# project.net
KiCad netlist of a schematic drawn in EAGLE
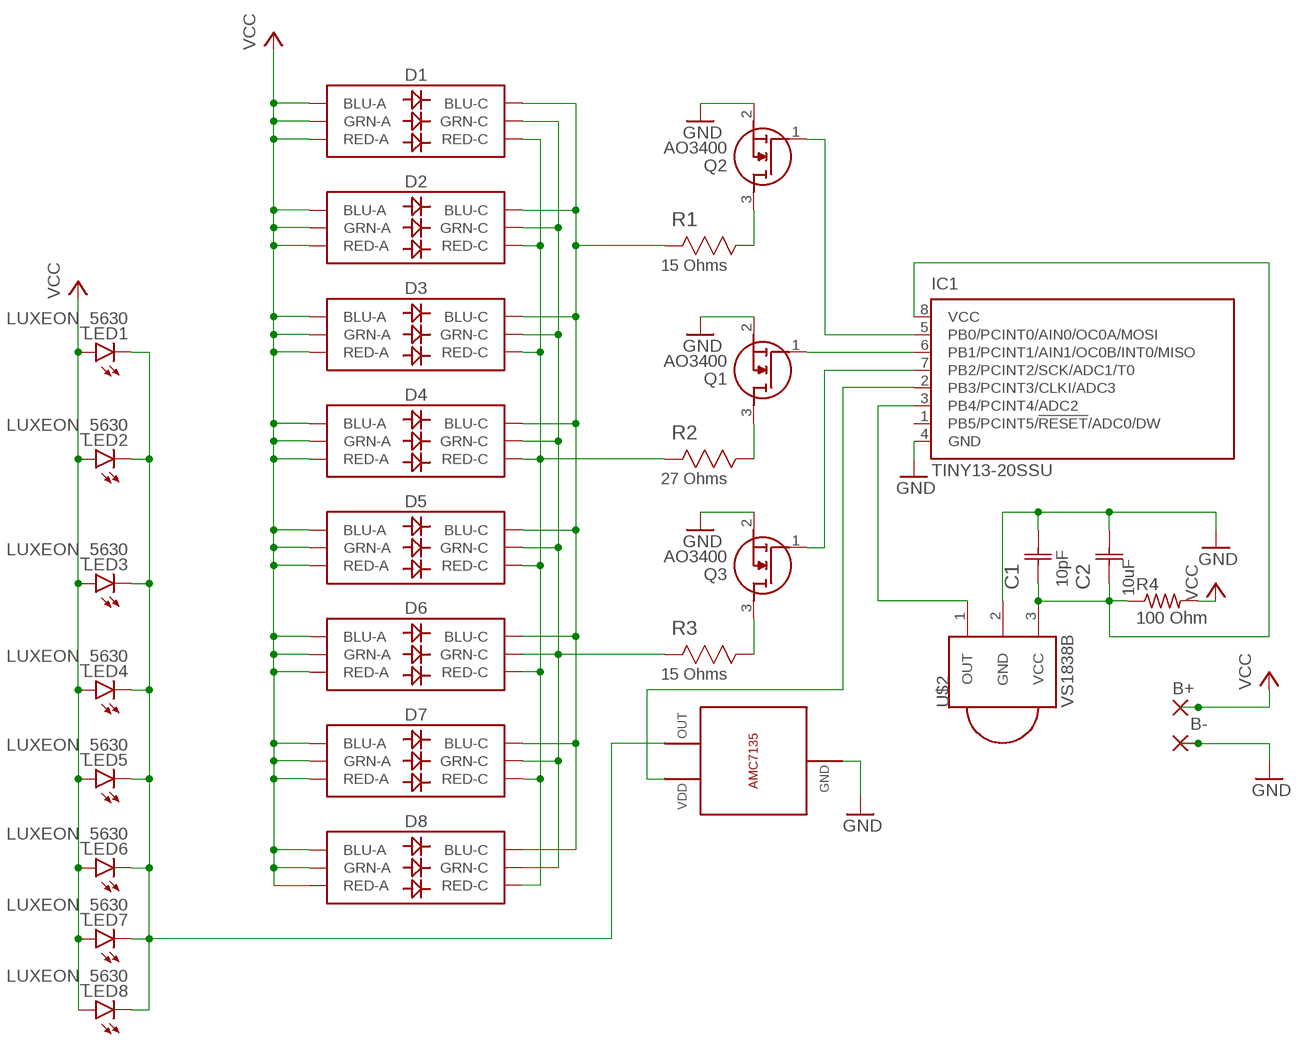
[diagram p0: schematic, sheet 1]

(export (version "E")
  (design (tool "Eeschema 10.0.6"))
  (components
    (comp (ref "B+")
      (value "WIREPADSMD1,27-254")
      (footprint "eagle-import:SMD1,27-2,54")
      (libsource (lib "eagle-import") (part "WIREPADSMD1,27-254"))
    )
    (comp (ref "B-")
      (value "WIREPADSMD1,27-254")
      (footprint "eagle-import:SMD1,27-2,54")
      (libsource (lib "eagle-import") (part "WIREPADSMD1,27-254"))
    )
    (comp (ref "C1")
      (value "10pF")
      (footprint "eagle-import:CAPC2013X94N")
      (fields (field (name "MPN") "08051A100JAT2A") (field (name "TOLERANCE") "±5%"))
      (libsource (lib "eagle-import") (part "08051A100JAT2A"))
    )
    (comp (ref "C2")
      (value "10uF")
      (footprint "eagle-import:CAPC3216X94N")
      (fields (field (name "MPN") "12061A101JAT2A") (field (name "TOLERANCE") "±5%"))
      (libsource (lib "eagle-import") (part "12061A101JAT2A"))
    )
    (comp (ref "D1")
      (value "LED-RGBNO_IC")
      (footprint "eagle-import:LED-TRICOLOR-5050")
      (libsource (lib "eagle-import") (part "LED-RGBNO_IC"))
    )
    (comp (ref "D2")
      (value "LED-RGBNO_IC")
      (footprint "eagle-import:LED-TRICOLOR-5050")
      (libsource (lib "eagle-import") (part "LED-RGBNO_IC"))
    )
    (comp (ref "D3")
      (value "LED-RGBNO_IC")
      (footprint "eagle-import:LED-TRICOLOR-5050")
      (libsource (lib "eagle-import") (part "LED-RGBNO_IC"))
    )
    (comp (ref "D4")
      (value "LED-RGBNO_IC")
      (footprint "eagle-import:LED-TRICOLOR-5050")
      (libsource (lib "eagle-import") (part "LED-RGBNO_IC"))
    )
    (comp (ref "D5")
      (value "LED-RGBNO_IC")
      (footprint "eagle-import:LED-TRICOLOR-5050")
      (libsource (lib "eagle-import") (part "LED-RGBNO_IC"))
    )
    (comp (ref "D6")
      (value "LED-RGBNO_IC")
      (footprint "eagle-import:LED-TRICOLOR-5050")
      (libsource (lib "eagle-import") (part "LED-RGBNO_IC"))
    )
    (comp (ref "D7")
      (value "LED-RGBNO_IC")
      (footprint "eagle-import:LED-TRICOLOR-5050")
      (libsource (lib "eagle-import") (part "LED-RGBNO_IC"))
    )
    (comp (ref "D8")
      (value "LED-RGBNO_IC")
      (footprint "eagle-import:LED-TRICOLOR-5050")
      (libsource (lib "eagle-import") (part "LED-RGBNO_IC"))
    )
    (comp (ref "IC1")
      (value "TINY13-20SSU")
      (footprint "eagle-import:8S1")
      (fields (field (name "MPN") "ATTINY13-20SSU"))
      (libsource (lib "eagle-import") (part "TINY13SSU-20"))
    )
    (comp (ref "LED1")
      (value "LUXEON_5630")
      (footprint "eagle-import:LUXEON_5630")
      (libsource (lib "eagle-import") (part "LUXEON_5630"))
    )
    (comp (ref "LED2")
      (value "LUXEON_5630")
      (footprint "eagle-import:LUXEON_5630")
      (libsource (lib "eagle-import") (part "LUXEON_5630"))
    )
    (comp (ref "LED3")
      (value "LUXEON_5630")
      (footprint "eagle-import:LUXEON_5630")
      (libsource (lib "eagle-import") (part "LUXEON_5630"))
    )
    (comp (ref "LED4")
      (value "LUXEON_5630")
      (footprint "eagle-import:LUXEON_5630")
      (libsource (lib "eagle-import") (part "LUXEON_5630"))
    )
    (comp (ref "LED5")
      (value "LUXEON_5630")
      (footprint "eagle-import:LUXEON_5630")
      (libsource (lib "eagle-import") (part "LUXEON_5630"))
    )
    (comp (ref "LED6")
      (value "LUXEON_5630")
      (footprint "eagle-import:LUXEON_5630")
      (libsource (lib "eagle-import") (part "LUXEON_5630"))
    )
    (comp (ref "LED7")
      (value "LUXEON_5630")
      (footprint "eagle-import:LUXEON_5630")
      (libsource (lib "eagle-import") (part "LUXEON_5630"))
    )
    (comp (ref "LED8")
      (value "LUXEON_5630")
      (footprint "eagle-import:LUXEON_5630")
      (libsource (lib "eagle-import") (part "LUXEON_5630"))
    )
    (comp (ref "Q1")
      (value "AO3400")
      (footprint "eagle-import:SOT95P280X125-3N")
      (libsource (lib "eagle-import") (part "AO3400"))
    )
    (comp (ref "Q2")
      (value "AO3400")
      (footprint "eagle-import:SOT95P280X125-3N")
      (libsource (lib "eagle-import") (part "AO3400"))
    )
    (comp (ref "Q3")
      (value "AO3400")
      (footprint "eagle-import:SOT95P280X125-3N")
      (libsource (lib "eagle-import") (part "AO3400"))
    )
    (comp (ref "R1")
      (value "15 Ohms")
      (footprint "eagle-import:RESC3216X71N")
      (fields (field (name "MPN") "CRCW1206130RFKEA") (field (name "TOLERANCE") "±1%"))
      (libsource (lib "eagle-import") (part "CRCW1206130RFKEA"))
    )
    (comp (ref "R2")
      (value "27 Ohms")
      (footprint "eagle-import:RESC3216X71N")
      (fields (field (name "MPN") "CRCW1206130RFKEA") (field (name "TOLERANCE") "±1%"))
      (libsource (lib "eagle-import") (part "CRCW1206130RFKEA"))
    )
    (comp (ref "R3")
      (value "15 Ohms")
      (footprint "eagle-import:RESC3216X71N")
      (fields (field (name "MPN") "CRCW1206130RFKEA") (field (name "TOLERANCE") "±1%"))
      (libsource (lib "eagle-import") (part "CRCW1206130RFKEA"))
    )
    (comp (ref "R4")
      (value "100 Ohm")
      (footprint "eagle-import:R0805")
      (libsource (lib "eagle-import") (part "R-US_R0805"))
    )
    (comp (ref "U$1")
      (value "AMC7135")
      (footprint "eagle-import:AMC7135")
      (libsource (lib "eagle-import") (part "AMC7135"))
    )
    (comp (ref "U$2")
      (value "VS1838B")
      (footprint "eagle-import:PNA460XM")
      (libsource (lib "eagle-import") (part "PNA460XM"))
    )
  )
  (nets
    (net (code "1") (name "GND") (class "Default")
      (node (ref "B-") (pin "1") (pinfunction "P_1") (pintype "passive"))
      (node (ref "C1") (pin "2") (pinfunction "C2_2") (pintype "passive"))
      (node (ref "C2") (pin "2") (pinfunction "C2_2") (pintype "passive"))
      (node (ref "IC1") (pin "4") (pinfunction "GND_4") (pintype "power_in"))
      (node (ref "Q1") (pin "2") (pinfunction "S_2") (pintype "bidirectional"))
      (node (ref "Q2") (pin "2") (pinfunction "S_2") (pintype "bidirectional"))
      (node (ref "Q3") (pin "2") (pinfunction "S_2") (pintype "bidirectional"))
      (node (ref "U$1") (pin "GND") (pinfunction "GND_GND") (pintype "bidirectional"))
      (node (ref "U$1") (pin "TAB") (pinfunction "GND_TAB") (pintype "bidirectional"))
      (node (ref "U$2") (pin "2") (pinfunction "GND_2") (pintype "power_in"))
    )
    (net (code "2") (name "Net-(C1-C1)") (class "Default")
      (node (ref "C1") (pin "1") (pinfunction "C1_1") (pintype "passive"))
      (node (ref "C2") (pin "1") (pinfunction "C1_1") (pintype "passive"))
      (node (ref "IC1") (pin "8") (pinfunction "VCC_8") (pintype "power_in"))
      (node (ref "R4") (pin "1") (pinfunction "1_1") (pintype "passive"))
      (node (ref "U$2") (pin "3") (pinfunction "VCC_3") (pintype "power_in"))
    )
    (net (code "3") (name "Net-(D1-BLU-C)") (class "Default")
      (node (ref "D1") (pin "4") (pinfunction "BLU-C_4") (pintype "bidirectional"))
      (node (ref "D2") (pin "4") (pinfunction "BLU-C_4") (pintype "bidirectional"))
      (node (ref "D3") (pin "4") (pinfunction "BLU-C_4") (pintype "bidirectional"))
      (node (ref "D4") (pin "4") (pinfunction "BLU-C_4") (pintype "bidirectional"))
      (node (ref "D5") (pin "4") (pinfunction "BLU-C_4") (pintype "bidirectional"))
      (node (ref "D6") (pin "4") (pinfunction "BLU-C_4") (pintype "bidirectional"))
      (node (ref "D7") (pin "4") (pinfunction "BLU-C_4") (pintype "bidirectional"))
      (node (ref "D8") (pin "4") (pinfunction "BLU-C_4") (pintype "bidirectional"))
      (node (ref "R1") (pin "2") (pinfunction "R2_2") (pintype "passive"))
    )
    (net (code "4") (name "Net-(D1-GRN-C)") (class "Default")
      (node (ref "D1") (pin "6") (pinfunction "GRN-C_6") (pintype "bidirectional"))
      (node (ref "D2") (pin "6") (pinfunction "GRN-C_6") (pintype "bidirectional"))
      (node (ref "D3") (pin "6") (pinfunction "GRN-C_6") (pintype "bidirectional"))
      (node (ref "D4") (pin "6") (pinfunction "GRN-C_6") (pintype "bidirectional"))
      (node (ref "D5") (pin "6") (pinfunction "GRN-C_6") (pintype "bidirectional"))
      (node (ref "D6") (pin "6") (pinfunction "GRN-C_6") (pintype "bidirectional"))
      (node (ref "D7") (pin "6") (pinfunction "GRN-C_6") (pintype "bidirectional"))
      (node (ref "D8") (pin "6") (pinfunction "GRN-C_6") (pintype "bidirectional"))
      (node (ref "R3") (pin "2") (pinfunction "R2_2") (pintype "passive"))
    )
    (net (code "5") (name "Net-(D1-RED-C)") (class "Default")
      (node (ref "D1") (pin "5") (pinfunction "RED-C_5") (pintype "bidirectional"))
      (node (ref "D2") (pin "5") (pinfunction "RED-C_5") (pintype "bidirectional"))
      (node (ref "D3") (pin "5") (pinfunction "RED-C_5") (pintype "bidirectional"))
      (node (ref "D4") (pin "5") (pinfunction "RED-C_5") (pintype "bidirectional"))
      (node (ref "D5") (pin "5") (pinfunction "RED-C_5") (pintype "bidirectional"))
      (node (ref "D6") (pin "5") (pinfunction "RED-C_5") (pintype "bidirectional"))
      (node (ref "D7") (pin "5") (pinfunction "RED-C_5") (pintype "bidirectional"))
      (node (ref "D8") (pin "5") (pinfunction "RED-C_5") (pintype "bidirectional"))
      (node (ref "R2") (pin "2") (pinfunction "R2_2") (pintype "passive"))
    )
    (net (code "6") (name "Net-(IC1-PB0{slash}PCINT0{slash}AIN0{slash}OC0A{slash}MOSI)") (class "Default")
      (node (ref "IC1") (pin "5") (pinfunction "PB0/PCINT0/AIN0/OC0A/MOSI_5") (pintype "bidirectional"))
      (node (ref "Q2") (pin "1") (pinfunction "G_1") (pintype "bidirectional"))
    )
    (net (code "7") (name "Net-(IC1-PB1{slash}PCINT1{slash}AIN1{slash}OC0B{slash}INT0{slash}MISO)") (class "Default")
      (node (ref "IC1") (pin "6") (pinfunction "PB1/PCINT1/AIN1/OC0B/INT0/MISO_6") (pintype "bidirectional"))
      (node (ref "Q1") (pin "1") (pinfunction "G_1") (pintype "bidirectional"))
    )
    (net (code "8") (name "Net-(IC1-PB2{slash}PCINT2{slash}SCK{slash}ADC1{slash}T0)") (class "Default")
      (node (ref "IC1") (pin "7") (pinfunction "PB2/PCINT2/SCK/ADC1/T0_7") (pintype "bidirectional"))
      (node (ref "Q3") (pin "1") (pinfunction "G_1") (pintype "bidirectional"))
    )
    (net (code "9") (name "Net-(IC1-PB3{slash}PCINT3{slash}CLKI{slash}ADC3)") (class "Default")
      (node (ref "IC1") (pin "2") (pinfunction "PB3/PCINT3/CLKI/ADC3_2") (pintype "bidirectional"))
      (node (ref "U$1") (pin "VDD") (pinfunction "VDD_VDD") (pintype "bidirectional"))
    )
    (net (code "10") (name "Net-(IC1-PB4{slash}PCINT4{slash}ADC2)") (class "Default")
      (node (ref "IC1") (pin "3") (pinfunction "PB4/PCINT4/ADC2_3") (pintype "bidirectional"))
      (node (ref "U$2") (pin "1") (pinfunction "OUT_1") (pintype "output"))
    )
    (net (code "11") (name "Net-(LED1-C-Pad1@1)") (class "Default")
      (node (ref "LED1") (pin "1@1") (pinfunction "C_1@1") (pintype "passive"))
      (node (ref "LED1") (pin "1@2") (pinfunction "C_1@2") (pintype "passive"))
      (node (ref "LED2") (pin "1@1") (pinfunction "C_1@1") (pintype "passive"))
      (node (ref "LED2") (pin "1@2") (pinfunction "C_1@2") (pintype "passive"))
      (node (ref "LED3") (pin "1@1") (pinfunction "C_1@1") (pintype "passive"))
      (node (ref "LED3") (pin "1@2") (pinfunction "C_1@2") (pintype "passive"))
      (node (ref "LED4") (pin "1@1") (pinfunction "C_1@1") (pintype "passive"))
      (node (ref "LED4") (pin "1@2") (pinfunction "C_1@2") (pintype "passive"))
      (node (ref "LED5") (pin "1@1") (pinfunction "C_1@1") (pintype "passive"))
      (node (ref "LED5") (pin "1@2") (pinfunction "C_1@2") (pintype "passive"))
      (node (ref "LED6") (pin "1@1") (pinfunction "C_1@1") (pintype "passive"))
      (node (ref "LED6") (pin "1@2") (pinfunction "C_1@2") (pintype "passive"))
      (node (ref "LED7") (pin "1@1") (pinfunction "C_1@1") (pintype "passive"))
      (node (ref "LED7") (pin "1@2") (pinfunction "C_1@2") (pintype "passive"))
      (node (ref "LED8") (pin "1@1") (pinfunction "C_1@1") (pintype "passive"))
      (node (ref "LED8") (pin "1@2") (pinfunction "C_1@2") (pintype "passive"))
      (node (ref "U$1") (pin "OUT") (pinfunction "OUT_OUT") (pintype "bidirectional"))
    )
    (net (code "12") (name "Net-(Q1-D)") (class "Default")
      (node (ref "Q1") (pin "3") (pinfunction "D_3") (pintype "bidirectional"))
      (node (ref "R2") (pin "1") (pinfunction "R1_1") (pintype "passive"))
    )
    (net (code "13") (name "Net-(Q2-D)") (class "Default")
      (node (ref "Q2") (pin "3") (pinfunction "D_3") (pintype "bidirectional"))
      (node (ref "R1") (pin "1") (pinfunction "R1_1") (pintype "passive"))
    )
    (net (code "14") (name "Net-(Q3-D)") (class "Default")
      (node (ref "Q3") (pin "3") (pinfunction "D_3") (pintype "bidirectional"))
      (node (ref "R3") (pin "1") (pinfunction "R1_1") (pintype "passive"))
    )
    (net (code "15") (name "VCC") (class "Default")
      (node (ref "B+") (pin "1") (pinfunction "P_1") (pintype "passive"))
      (node (ref "D1") (pin "1") (pinfunction "GRN-A_1") (pintype "bidirectional"))
      (node (ref "D1") (pin "2") (pinfunction "RED-A_2") (pintype "bidirectional"))
      (node (ref "D1") (pin "3") (pinfunction "BLU-A_3") (pintype "bidirectional"))
      (node (ref "D2") (pin "1") (pinfunction "GRN-A_1") (pintype "bidirectional"))
      (node (ref "D2") (pin "2") (pinfunction "RED-A_2") (pintype "bidirectional"))
      (node (ref "D2") (pin "3") (pinfunction "BLU-A_3") (pintype "bidirectional"))
      (node (ref "D3") (pin "1") (pinfunction "GRN-A_1") (pintype "bidirectional"))
      (node (ref "D3") (pin "2") (pinfunction "RED-A_2") (pintype "bidirectional"))
      (node (ref "D3") (pin "3") (pinfunction "BLU-A_3") (pintype "bidirectional"))
      (node (ref "D4") (pin "1") (pinfunction "GRN-A_1") (pintype "bidirectional"))
      (node (ref "D4") (pin "2") (pinfunction "RED-A_2") (pintype "bidirectional"))
      (node (ref "D4") (pin "3") (pinfunction "BLU-A_3") (pintype "bidirectional"))
      (node (ref "D5") (pin "1") (pinfunction "GRN-A_1") (pintype "bidirectional"))
      (node (ref "D5") (pin "2") (pinfunction "RED-A_2") (pintype "bidirectional"))
      (node (ref "D5") (pin "3") (pinfunction "BLU-A_3") (pintype "bidirectional"))
      (node (ref "D6") (pin "1") (pinfunction "GRN-A_1") (pintype "bidirectional"))
      (node (ref "D6") (pin "2") (pinfunction "RED-A_2") (pintype "bidirectional"))
      (node (ref "D6") (pin "3") (pinfunction "BLU-A_3") (pintype "bidirectional"))
      (node (ref "D7") (pin "1") (pinfunction "GRN-A_1") (pintype "bidirectional"))
      (node (ref "D7") (pin "2") (pinfunction "RED-A_2") (pintype "bidirectional"))
      (node (ref "D7") (pin "3") (pinfunction "BLU-A_3") (pintype "bidirectional"))
      (node (ref "D8") (pin "1") (pinfunction "GRN-A_1") (pintype "bidirectional"))
      (node (ref "D8") (pin "2") (pinfunction "RED-A_2") (pintype "bidirectional"))
      (node (ref "D8") (pin "3") (pinfunction "BLU-A_3") (pintype "bidirectional"))
      (node (ref "LED1") (pin "2") (pinfunction "A_2") (pintype "passive"))
      (node (ref "LED2") (pin "2") (pinfunction "A_2") (pintype "passive"))
      (node (ref "LED3") (pin "2") (pinfunction "A_2") (pintype "passive"))
      (node (ref "LED4") (pin "2") (pinfunction "A_2") (pintype "passive"))
      (node (ref "LED5") (pin "2") (pinfunction "A_2") (pintype "passive"))
      (node (ref "LED6") (pin "2") (pinfunction "A_2") (pintype "passive"))
      (node (ref "LED7") (pin "2") (pinfunction "A_2") (pintype "passive"))
      (node (ref "LED8") (pin "2") (pinfunction "A_2") (pintype "passive"))
      (node (ref "R4") (pin "2") (pinfunction "2_2") (pintype "passive"))
    )
    (net (code "16") (name "unconnected-(IC1-PB5{slash}PCINT5{slash}~{RESET}{slash}ADC0{slash}DW-Pad1)") (class "Default")
      (node (ref "IC1") (pin "1") (pinfunction "PB5/PCINT5/~{RESET}/ADC0/DW_1") (pintype "bidirectional"))
    )
  )
)
